# 03-POWER.net
KiCad netlist of a schematic drawn in Altium Designer
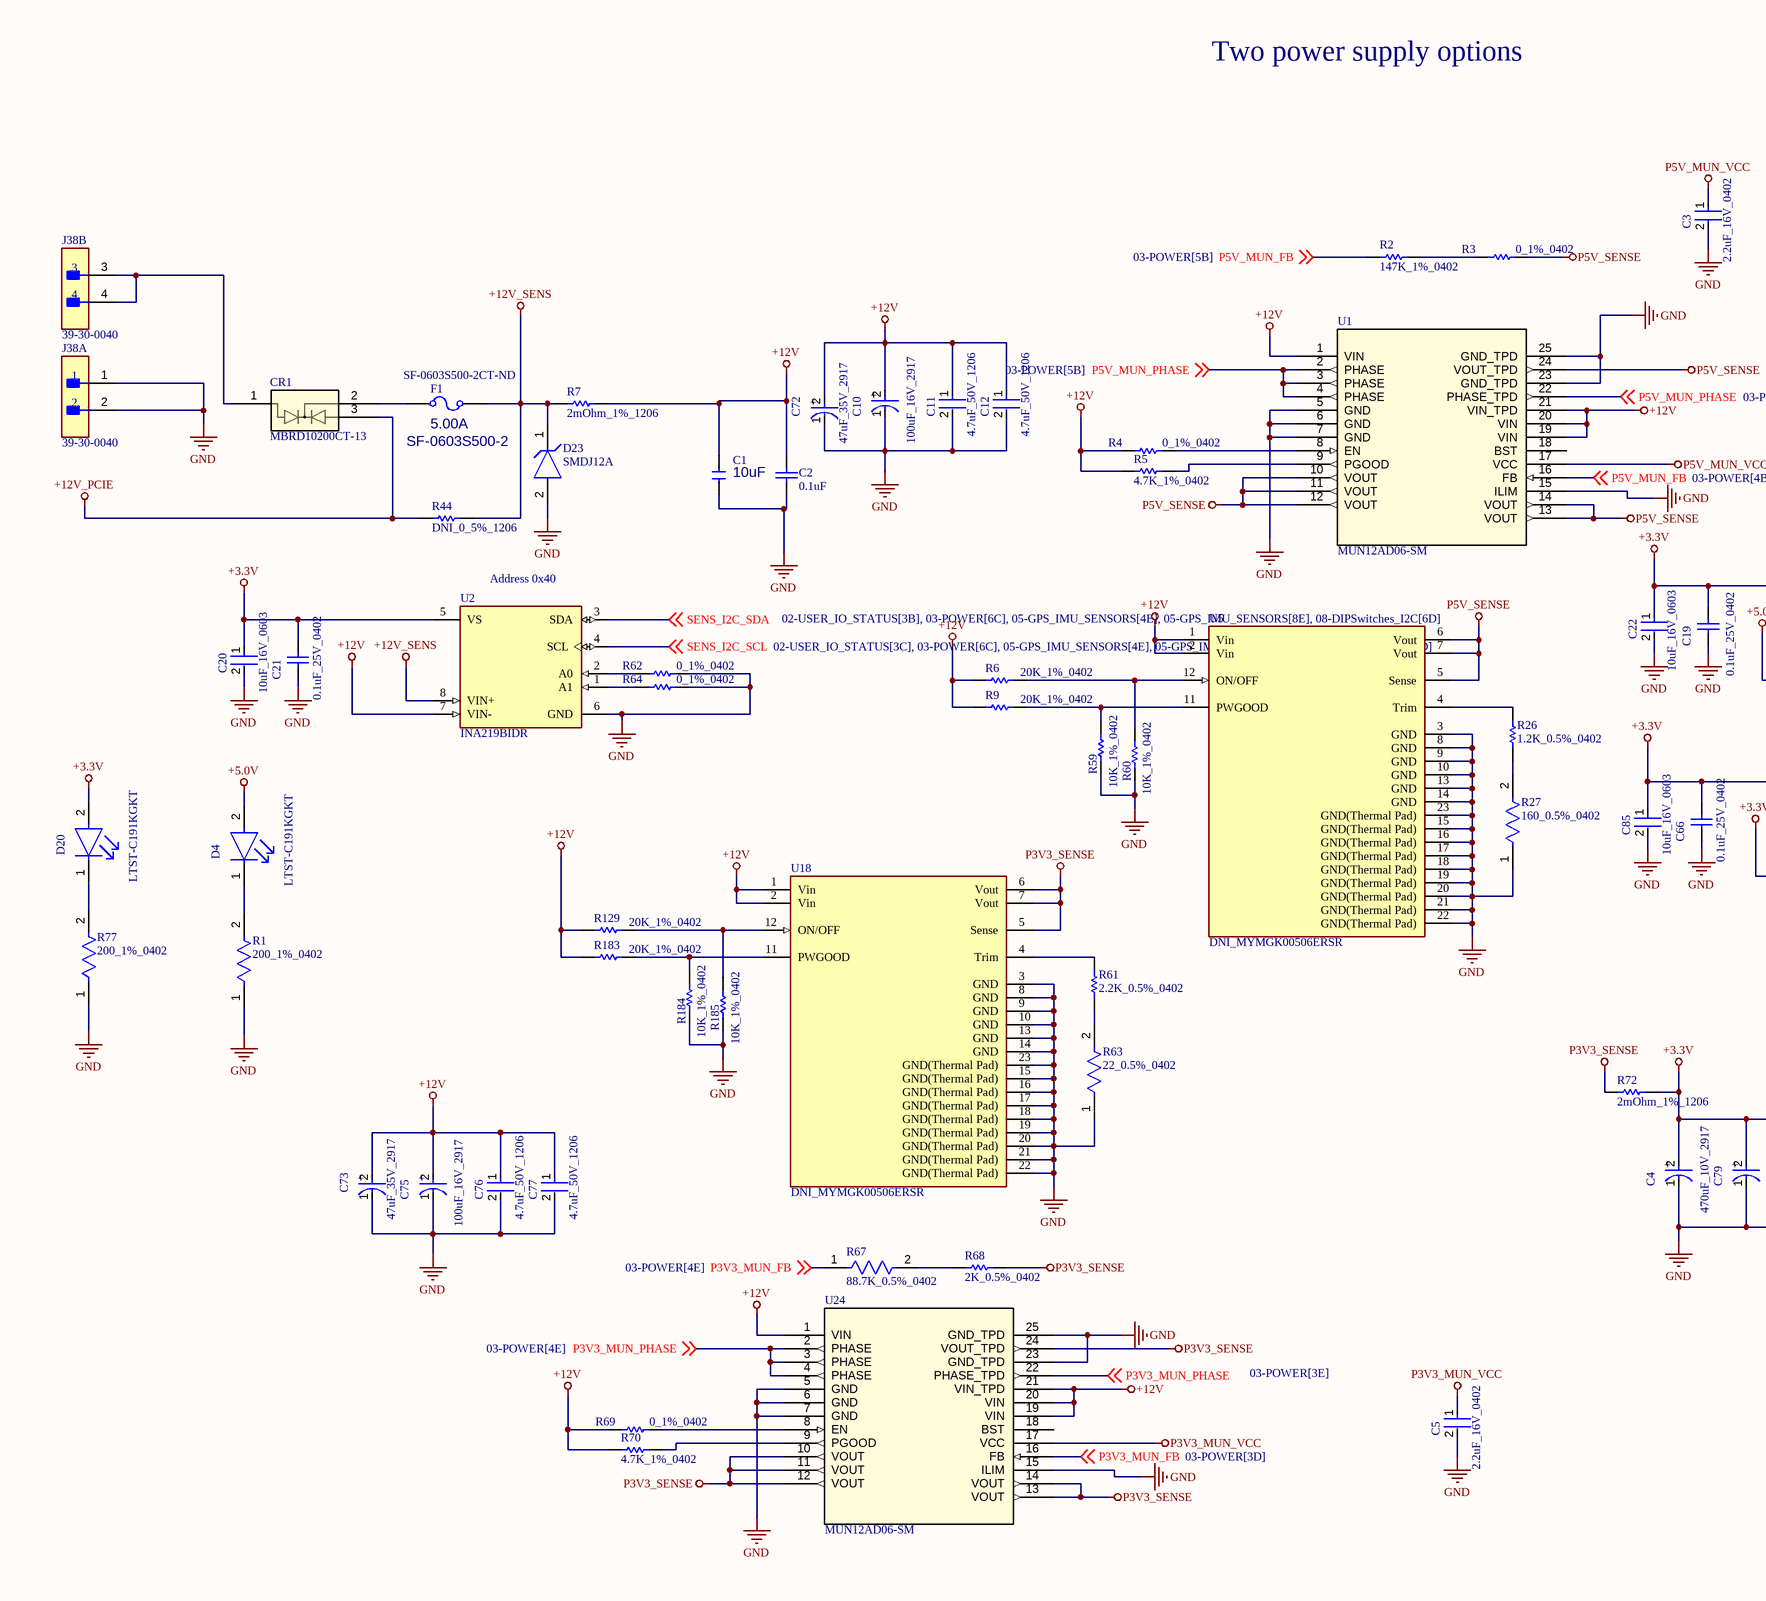
[diagram p0: 03-POWER.SchDoc, left]
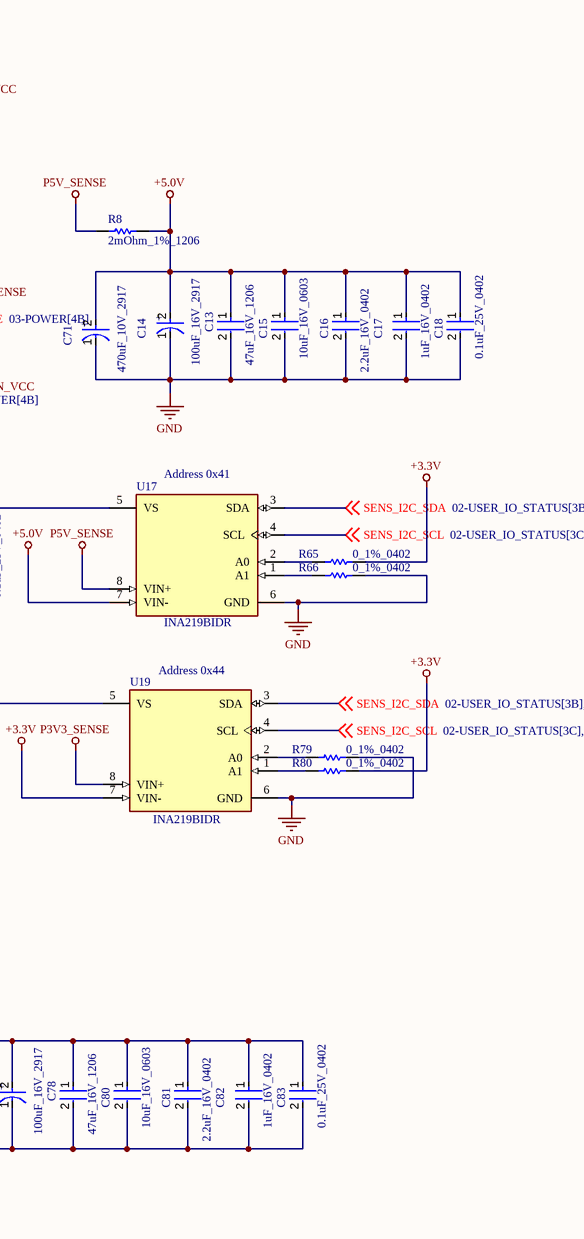
[diagram p1: 03-POWER.SchDoc, right]

(export (version "E")
  (design (tool "Eeschema 10.0.6"))
  (components
    (comp (ref "C1")
      (value "10uF")
      (footprint "CAPC2012X14N")
      (description "CAP, CER, 10.UF, 25V, 10%, X5R, 0805")
      (fields
        (field (name "MFG PART NUM") "TMK212BBJ106KG-T")
        (field (name "VALENTIUM PART NUM") "<VALENTIUM>")
      )
      (libsource (lib "Capacitors") (part "CAP_0805_10UF_25V"))
    )
    (comp (ref "C2")
      (value "0.1uF")
      (footprint "CAPC1608X87X45ML20T05")
      (description "C0603X104K5RACAUTO")
      (fields (field (name "MANUFACTURER") "Kemet"))
      (libsource (lib "Altium Content Vault") (part "CAP"))
    )
    (comp (ref "C3")
      (value "2.2uF_16V_0402")
      (footprint "FP-C1005-050-0_05-IPC_A")
      (description "Multilayer Ceramic Capacitors 2.2μF ±10% 16V X5R SMD 0402")
      (fields (field (name "TOLERANCE") "10%"))
      (libsource (lib "Altium Content Vault") (part "b4654b650e69147ec39a6b967a45e02"))
    )
    (comp (ref "C4")
      (value "470uF_10V_2917")
      (footprint "FP-TAJE-MFG")
      (description "470uF 10V  ±10% 500mΩ 2917  SMD Tantalum Capacitor")
      (fields (field (name "TOLERANCE") "10%") (field (name "VOLTAGE") "10V"))
      (libsource (lib "Altium Content Vault") (part "203bc49f2ac43e59fd269a8c329ed05"))
    )
    (comp (ref "C5")
      (value "2.2uF_16V_0402")
      (footprint "FP-C1005-050-0_05-IPC_A")
      (description "Multilayer Ceramic Capacitors 2.2μF ±10% 16V X5R SMD 0402")
      (fields (field (name "TOLERANCE") "10%"))
      (libsource (lib "Altium Content Vault") (part "b4654b650e69147ec39a6b967a45e02"))
    )
    (comp (ref "C10")
      (value "100uF_16V_2917")
      (footprint "FP-T495D107K016ATE125-MFG")
      (description "CAP TANT 100UF 10% 16V 2917")
      (fields (field (name "VOLTAGE") "16V") (field (name "TOLERANCE") "10%"))
      (libsource (lib "Altium Content Vault") (part "a00bbbee19879c290e62620ae7e47b1"))
    )
    (comp (ref "C11")
      (value "4.7uF_50V_1206")
      (footprint "FP-GRM31C-0_2-e0_3_0_8-IPC_C")
      (description "Chip Multilayer Ceramic Capacitors for General Purpose, 1206, 4.7uF, X7R, 15%, 10%, 50V")
      (fields (field (name "VOLTAGE") "50V") (field (name "TOLERANCE") "10%"))
      (libsource (lib "Altium Content Vault") (part "02cd4be3c70576c341d710602a673aa"))
    )
    (comp (ref "C12")
      (value "4.7uF_50V_1206")
      (footprint "FP-GRM31C-0_2-e0_3_0_8-IPC_C")
      (description "Chip Multilayer Ceramic Capacitors for General Purpose, 1206, 4.7uF, X7R, 15%, 10%, 50V")
      (fields (field (name "VOLTAGE") "50V") (field (name "TOLERANCE") "10%"))
      (libsource (lib "Altium Content Vault") (part "02cd4be3c70576c341d710602a673aa"))
    )
    (comp (ref "C13")
      (value "47uF_16V_1206")
      (footprint "FP-C3216-160-0_2-MFG")
      (description "Multilayer Ceramic Capacitors 47uF ±20% 16V X5R SMD 1206")
      (fields (field (name "TOLERANCE") "20%"))
      (libsource (lib "Altium Content Vault") (part "11868f565c42a9108669ba33697ecf6"))
    )
    (comp (ref "C14")
      (value "100uF_16V_2917")
      (footprint "FP-T495D107K016ATE125-MFG")
      (description "CAP TANT 100UF 10% 16V 2917")
      (fields (field (name "VOLTAGE") "16V") (field (name "TOLERANCE") "10%"))
      (libsource (lib "Altium Content Vault") (part "a00bbbee19879c290e62620ae7e47b1"))
    )
    (comp (ref "C15")
      (value "10uF_16V_0603")
      (footprint "FP-0603-L_1_6_0_2-W_0_8_0-MFG")
      (description "Multilayer Ceramic Capacitor 10uF 16V X5R 20% SMD 0603 T/R")
      (fields (field (name "TOLERANCE") "20%"))
      (libsource (lib "Altium Content Vault") (part "b4654b650e69147ec39a6b967a45e02"))
    )
    (comp (ref "C16")
      (value "2.2uF_16V_0402")
      (footprint "FP-C1005-050-0_05-IPC_A")
      (description "Multilayer Ceramic Capacitors 2.2μF ±10% 16V X5R SMD 0402")
      (fields (field (name "TOLERANCE") "10%"))
      (libsource (lib "Altium Content Vault") (part "b4654b650e69147ec39a6b967a45e02"))
    )
    (comp (ref "C17")
      (value "1uF_16V_0402")
      (footprint "FP-0402-L_1_0_0_05-W_0_5-IPC_A")
      (description "None")
      (fields (field (name "TOLERANCE") "10%"))
      (libsource (lib "Altium Content Vault") (part "b4654b650e69147ec39a6b967a45e02"))
    )
    (comp (ref "C18")
      (value "0.1uF_25V_0402")
      (footprint "FP-0402-L_1_0_1-W_0_5_0_1-IPC_C")
      (description "General Purpose Ceramic Capacitor, 0402, 100nF, 10%, X7R, 15%, 25V")
      (fields (field (name "VOLTAGE") "25V") (field (name "TOLERANCE") "10%"))
      (libsource (lib "Altium Content Vault") (part "b4654b650e69147ec39a6b967a45e02"))
    )
    (comp (ref "C19")
      (value "0.1uF_25V_0402")
      (footprint "CAPC1005X56X25NL10T15")
      (fields
        (field (name "PART NUMBER") "04023D104KAT2A")
        (field (name "MANUFACTURER") "AVX Interconnect / Elco")
      )
      (libsource (lib "Altium Content Vault") (part "CAP"))
    )
    (comp (ref "C20")
      (value "10uF_16V_0603")
      (footprint "FP-0603-L_1_6_0_2-W_0_8_0-MFG")
      (description "Multilayer Ceramic Capacitor 10uF 16V X5R 20% SMD 0603 T/R")
      (fields (field (name "TOLERANCE") "20%"))
      (libsource (lib "Altium Content Vault") (part "b4654b650e69147ec39a6b967a45e02"))
    )
    (comp (ref "C21")
      (value "0.1uF_25V_0402")
      (footprint "CAPC1005X56X25NL10T15")
      (fields
        (field (name "PART NUMBER") "04023D104KAT2A")
        (field (name "MANUFACTURER") "AVX Interconnect / Elco")
      )
      (libsource (lib "Altium Content Vault") (part "CAP"))
    )
    (comp (ref "C22")
      (value "10uF_16V_0603")
      (footprint "FP-0603-L_1_6_0_2-W_0_8_0-MFG")
      (description "Multilayer Ceramic Capacitor 10uF 16V X5R 20% SMD 0603 T/R")
      (fields (field (name "TOLERANCE") "20%"))
      (libsource (lib "Altium Content Vault") (part "b4654b650e69147ec39a6b967a45e02"))
    )
    (comp (ref "C66")
      (value "0.1uF_25V_0402")
      (footprint "CAPC1005X56X25NL10T15")
      (fields
        (field (name "PART NUMBER") "04023D104KAT2A")
        (field (name "MANUFACTURER") "AVX Interconnect / Elco")
      )
      (libsource (lib "Altium Content Vault") (part "CAP"))
    )
    (comp (ref "C71")
      (value "470uF_10V_2917")
      (footprint "FP-TAJE-MFG")
      (description "470uF 10V  ±10% 500mΩ 2917  SMD Tantalum Capacitor")
      (fields (field (name "TOLERANCE") "10%") (field (name "VOLTAGE") "10V"))
      (libsource (lib "Altium Content Vault") (part "203bc49f2ac43e59fd269a8c329ed05"))
    )
    (comp (ref "C72")
      (value "47uF_35V_2917")
      (footprint "FP-T521X476M035ATE030-MFG")
      (description "CAP TANT POLY 47UF 35V 2917")
      (fields (field (name "TOLERANCE") "20%"))
      (libsource (lib "Altium Content Vault") (part "a00bbbee19879c290e62620ae7e47b1"))
    )
    (comp (ref "C73")
      (value "47uF_35V_2917")
      (footprint "FP-T521X476M035ATE030-MFG")
      (description "CAP TANT POLY 47UF 35V 2917")
      (fields (field (name "TOLERANCE") "20%"))
      (libsource (lib "Altium Content Vault") (part "a00bbbee19879c290e62620ae7e47b1"))
    )
    (comp (ref "C75")
      (value "100uF_16V_2917")
      (footprint "FP-T495D107K016ATE125-MFG")
      (description "CAP TANT 100UF 10% 16V 2917")
      (fields (field (name "VOLTAGE") "16V") (field (name "TOLERANCE") "10%"))
      (libsource (lib "Altium Content Vault") (part "a00bbbee19879c290e62620ae7e47b1"))
    )
    (comp (ref "C76")
      (value "4.7uF_50V_1206")
      (footprint "FP-GRM31C-0_2-e0_3_0_8-IPC_C")
      (description "Chip Multilayer Ceramic Capacitors for General Purpose, 1206, 4.7uF, X7R, 15%, 10%, 50V")
      (fields (field (name "VOLTAGE") "50V") (field (name "TOLERANCE") "10%"))
      (libsource (lib "Altium Content Vault") (part "02cd4be3c70576c341d710602a673aa"))
    )
    (comp (ref "C77")
      (value "4.7uF_50V_1206")
      (footprint "FP-GRM31C-0_2-e0_3_0_8-IPC_C")
      (description "Chip Multilayer Ceramic Capacitors for General Purpose, 1206, 4.7uF, X7R, 15%, 10%, 50V")
      (fields (field (name "VOLTAGE") "50V") (field (name "TOLERANCE") "10%"))
      (libsource (lib "Altium Content Vault") (part "02cd4be3c70576c341d710602a673aa"))
    )
    (comp (ref "C78")
      (value "47uF_16V_1206")
      (footprint "FP-C3216-160-0_2-MFG")
      (description "Multilayer Ceramic Capacitors 47uF ±20% 16V X5R SMD 1206")
      (fields (field (name "TOLERANCE") "20%"))
      (libsource (lib "Altium Content Vault") (part "11868f565c42a9108669ba33697ecf6"))
    )
    (comp (ref "C79")
      (value "100uF_16V_2917")
      (footprint "FP-T495D107K016ATE125-MFG")
      (description "CAP TANT 100UF 10% 16V 2917")
      (fields (field (name "VOLTAGE") "16V") (field (name "TOLERANCE") "10%"))
      (libsource (lib "Altium Content Vault") (part "a00bbbee19879c290e62620ae7e47b1"))
    )
    (comp (ref "C80")
      (value "10uF_16V_0603")
      (footprint "FP-0603-L_1_6_0_2-W_0_8_0-MFG")
      (description "Multilayer Ceramic Capacitor 10uF 16V X5R 20% SMD 0603 T/R")
      (fields (field (name "TOLERANCE") "20%"))
      (libsource (lib "Altium Content Vault") (part "b4654b650e69147ec39a6b967a45e02"))
    )
    (comp (ref "C81")
      (value "2.2uF_16V_0402")
      (footprint "FP-C1005-050-0_05-IPC_A")
      (description "Multilayer Ceramic Capacitors 2.2μF ±10% 16V X5R SMD 0402")
      (fields (field (name "TOLERANCE") "10%"))
      (libsource (lib "Altium Content Vault") (part "b4654b650e69147ec39a6b967a45e02"))
    )
    (comp (ref "C82")
      (value "1uF_16V_0402")
      (footprint "FP-0402-L_1_0_0_05-W_0_5-IPC_A")
      (description "None")
      (fields (field (name "TOLERANCE") "10%"))
      (libsource (lib "Altium Content Vault") (part "b4654b650e69147ec39a6b967a45e02"))
    )
    (comp (ref "C83")
      (value "0.1uF_25V_0402")
      (footprint "FP-0402-L_1_0_1-W_0_5_0_1-IPC_C")
      (description "General Purpose Ceramic Capacitor, 0402, 100nF, 10%, X7R, 15%, 25V")
      (fields (field (name "VOLTAGE") "25V") (field (name "TOLERANCE") "10%"))
      (libsource (lib "Altium Content Vault") (part "b4654b650e69147ec39a6b967a45e02"))
    )
    (comp (ref "C85")
      (value "10uF_16V_0603")
      (footprint "FP-0603-L_1_6_0_2-W_0_8_0-MFG")
      (description "Multilayer Ceramic Capacitor 10uF 16V X5R 20% SMD 0603 T/R")
      (fields (field (name "TOLERANCE") "20%"))
      (libsource (lib "Altium Content Vault") (part "b4654b650e69147ec39a6b967a45e02"))
    )
    (comp (ref "CR1")
      (value "MBRD10200CT-13")
      (footprint "TO252(DPAK)_DIO")
      (description "No Description Available")
      (libsource (lib "MBRD10200CT-13") (part "MBRD10200CT-13"))
    )
    (comp (ref "D4")
      (value "LTST-C191KGKT")
      (footprint "FP-LTST-C191KGKT-MFG")
      (description "LED GREEN CLEAR SMD")
      (libsource (lib "Altium Content Vault") (part "8706943c75ba83719d021d2fdc84c58"))
    )
    (comp (ref "D20")
      (value "LTST-C191KGKT")
      (footprint "FP-LTST-C191KGKT-MFG")
      (description "LED GREEN CLEAR SMD")
      (libsource (lib "Altium Content Vault") (part "8706943c75ba83719d021d2fdc84c58"))
    )
    (comp (ref "D23")
      (value "SMDJ12A")
      (footprint "FP-DO-214AB_SMC_J-Bend-MFG")
      (description "TVS DIODE 12V 19.9V DO214AB")
      (libsource (lib "Altium Content Vault") (part "673ecd2ea4d7fb87b4005b0cb348b7d"))
    )
    (comp (ref "F1")
      (value "5.00A")
      (footprint "FUSM1608X60N")
      (description "FUSE SLOW 5.00A 32V M 0603")
      (fields
        (field (name "MFG PART NUM") "SF-0603S500-2")
        (field (name "VALENTIUM PART NUM") "<VALENTIUM>")
        (field (name "SUPPLIER PART NUMBER 1") "SF-0603S500-2CT-ND")
        (field (name "Comment") "FUSE_0603_5.00A")
      )
      (libsource (lib "Passives") (part "FUSE_0603_2.00A"))
    )
    (comp (ref "J38")
      (value "39-30-0040")
      (footprint "FP-39-30-0040-MFG")
      (description "CONN HEADER R/A 4POS 4.2MM")
      (fields
        (field (name "OCTOPART") "https://octopart.com/39-30-0040-molex-277428")
        (field (name "MANUFACTURER") "Molex")
      )
      (libsource (lib "Altium Content Vault") (part "ac72c5313ea981db199dbd0e8237b04"))
    )
    (comp (ref "R1")
      (value "200_1%_0402")
      (footprint "FP-ERJ2RK-IPC_A")
      (description "RES SMD 200 OHM 1% 1/10W 0402")
      (fields (field (name "TOLERANCE") "1%"))
      (libsource (lib "Altium Content Vault") (part "1029c3af85768c4190bb7ad29bc67b5"))
    )
    (comp (ref "R2")
      (value "147K_1%_0402")
      (footprint "RESC1005X40X25ML05T10")
      (fields (field (name "MANUFACTURER") "Yageo / Phycomp") (field (name "PART NUMBER") "RC0402FR-07147KL"))
      (libsource (lib "Altium Content Vault") (part "RES"))
    )
    (comp (ref "R3")
      (value "0_1%_0402")
      (footprint "RESC1005X40X25LL05T05")
      (description "Chip Resistor, 0 Ohm, 0.1 W, -55 to 155 degC, 0402 (1005 Metric), RoHS, Tape and Reel")
      (fields (field (name "MANUFACTURER") "Panasonic") (field (name "TOLERANCE") "5%"))
      (libsource (lib "Altium Content Vault") (part "RES-2"))
    )
    (comp (ref "R4")
      (value "0_1%_0402")
      (footprint "RESC1005X40X25LL05T05")
      (description "Chip Resistor, 0 Ohm, 0.1 W, -55 to 155 degC, 0402 (1005 Metric), RoHS, Tape and Reel")
      (fields (field (name "MANUFACTURER") "Panasonic") (field (name "TOLERANCE") "5%"))
      (libsource (lib "Altium Content Vault") (part "RES-2"))
    )
    (comp (ref "R5")
      (value "4.7K_1%_0402")
      (footprint "RESC1005X40X25NL10T10")
      (fields (field (name "MANUFACTURER") "Bourns") (field (name "PART NUMBER") "CR0402-FX-4701GLF"))
      (libsource (lib "Altium Content Vault") (part "RES"))
    )
    (comp (ref "R6")
      (value "20K_1%_0402")
      (footprint "RESC1005X40X25NL10T10")
      (fields (field (name "PART NUMBER") "MC00625W0402120K") (field (name "MANUFACTURER") "Multicomp"))
      (libsource (lib "Altium Content Vault") (part "RES"))
    )
    (comp (ref "R7")
      (value "2mOhm_1%_1206")
      (footprint "RESC3216X89X64NL25T25")
      (fields (field (name "MANUFACTURER") "Vishay Dale") (field (name "PART NUMBER") "WSL12062L000FEA18"))
      (libsource (lib "Altium Content Vault") (part "RES"))
    )
    (comp (ref "R8")
      (value "2mOhm_1%_1206")
      (footprint "RESC3216X89X64NL25T25")
      (fields (field (name "MANUFACTURER") "Vishay Dale") (field (name "PART NUMBER") "WSL12062L000FEA18"))
      (libsource (lib "Altium Content Vault") (part "RES"))
    )
    (comp (ref "R9")
      (value "20K_1%_0402")
      (footprint "RESC1005X40X25NL10T10")
      (fields (field (name "PART NUMBER") "MC00625W0402120K") (field (name "MANUFACTURER") "Multicomp"))
      (libsource (lib "Altium Content Vault") (part "RES"))
    )
    (comp (ref "R26")
      (value "1.2K_0.5%_0402")
      (footprint "RESC1005X40X25ML10T10")
      (fields (field (name "PART NUMBER") "ERA-2AED122X") (field (name "MANUFACTURER") "Panasonic"))
      (libsource (lib "Altium Content Vault") (part "RES"))
    )
    (comp (ref "R27")
      (value "160_0.5%_0402")
      (footprint "FP-RT0402-MFG")
      (description "RES SMD 160 OHM 0.5% 1/16W 0402")
      (fields
        (field (name "TOLERANCE") "0.005")
        (field (name "OCTOPART") "https://octopart.com/rt0402dre07160rl-yageo-1216058")
      )
      (libsource (lib "Altium Content Vault") (part "1029c3af85768c4190bb7ad29bc67b5"))
    )
    (comp (ref "R44")
      (value "DNI_0_5%_1206")
      (footprint "RESC3116X65X50ML20T20")
      (fields (field (name "PART NUMBER") "CRCW12060000Z0EAHP") (field (name "MANUFACTURER") "Vishay Dale"))
      (libsource (lib "Altium Content Vault") (part "RES"))
    )
    (comp (ref "R59")
      (value "10K_1%_0402")
      (footprint "RESC1005X40X25NL10T10")
      (fields (field (name "MANUFACTURER") "Bourns") (field (name "PART NUMBER") "CR0402-FX-1002GLF"))
      (libsource (lib "Altium Content Vault") (part "RES"))
    )
    (comp (ref "R60")
      (value "10K_1%_0402")
      (footprint "RESC1005X40X25NL10T10")
      (fields (field (name "MANUFACTURER") "Bourns") (field (name "PART NUMBER") "CR0402-FX-1002GLF"))
      (libsource (lib "Altium Content Vault") (part "RES"))
    )
    (comp (ref "R61")
      (value "2.2K_0.5%_0402")
      (footprint "RESC1005X40X25ML10T10")
      (fields (field (name "PART NUMBER") "ERA-2AED222X") (field (name "MANUFACTURER") "Panasonic"))
      (libsource (lib "Altium Content Vault") (part "RES"))
    )
    (comp (ref "R62")
      (value "0_1%_0402")
      (footprint "RESC1005X40X25LL05T05")
      (description "Chip Resistor, 0 Ohm, 0.1 W, -55 to 155 degC, 0402 (1005 Metric), RoHS, Tape and Reel")
      (fields (field (name "MANUFACTURER") "Panasonic") (field (name "TOLERANCE") "5%"))
      (libsource (lib "Altium Content Vault") (part "RES-2"))
    )
    (comp (ref "R63")
      (value "22_0.5%_0402")
      (footprint "FP-RG1005-IPC_A")
      (description "Automotive Metal Thin Film Chip Resistor, 0402, 22Ω, 0.5%, 100ppm/°C, 0.0625W, 75V")
      (fields (field (name "TOLERANCE") "0.5%"))
      (libsource (lib "Altium Content Vault") (part "1029c3af85768c4190bb7ad29bc67b5"))
    )
    (comp (ref "R64")
      (value "0_1%_0402")
      (footprint "RESC1005X40X25LL05T05")
      (description "Chip Resistor, 0 Ohm, 0.1 W, -55 to 155 degC, 0402 (1005 Metric), RoHS, Tape and Reel")
      (fields (field (name "MANUFACTURER") "Panasonic") (field (name "TOLERANCE") "5%"))
      (libsource (lib "Altium Content Vault") (part "RES-2"))
    )
    (comp (ref "R65")
      (value "0_1%_0402")
      (footprint "RESC1005X40X25LL05T05")
      (description "Chip Resistor, 0 Ohm, 0.1 W, -55 to 155 degC, 0402 (1005 Metric), RoHS, Tape and Reel")
      (fields (field (name "MANUFACTURER") "Panasonic") (field (name "TOLERANCE") "5%"))
      (libsource (lib "Altium Content Vault") (part "RES-2"))
    )
    (comp (ref "R66")
      (value "0_1%_0402")
      (footprint "RESC1005X40X25LL05T05")
      (description "Chip Resistor, 0 Ohm, 0.1 W, -55 to 155 degC, 0402 (1005 Metric), RoHS, Tape and Reel")
      (fields (field (name "MANUFACTURER") "Panasonic") (field (name "TOLERANCE") "5%"))
      (libsource (lib "Altium Content Vault") (part "RES-2"))
    )
    (comp (ref "R67")
      (value "88.7K_0.5%_0402")
      (footprint "FP-RT0402-MFG")
      (description "RES SMD 88.7K OHM 0.5% 1/16W")
      (fields
        (field (name "OCTOPART") "https://octopart.com/rt0402dre0788k7l-yageo-1439224")
        (field (name "MANUFACTURER") "Yageo")
      )
      (libsource (lib "Altium Content Vault") (part "1029c3af85768c4190bb7ad29bc67b5"))
    )
    (comp (ref "R68")
      (value "2K_0.5%_0402")
      (footprint "RESC1005X35X25LL10T10")
      (fields (field (name "PART NUMBER") "RT0402DRD072KL") (field (name "MANUFACTURER") "Yageo"))
      (libsource (lib "Altium Content Vault") (part "RES"))
    )
    (comp (ref "R69")
      (value "0_1%_0402")
      (footprint "RESC1005X40X25LL05T05")
      (description "Chip Resistor, 0 Ohm, 0.1 W, -55 to 155 degC, 0402 (1005 Metric), RoHS, Tape and Reel")
      (fields (field (name "MANUFACTURER") "Panasonic") (field (name "TOLERANCE") "5%"))
      (libsource (lib "Altium Content Vault") (part "RES-2"))
    )
    (comp (ref "R70")
      (value "4.7K_1%_0402")
      (footprint "RESC1005X40X25NL10T10")
      (fields (field (name "MANUFACTURER") "Bourns") (field (name "PART NUMBER") "CR0402-FX-4701GLF"))
      (libsource (lib "Altium Content Vault") (part "RES"))
    )
    (comp (ref "R72")
      (value "2mOhm_1%_1206")
      (footprint "RESC3216X89X64NL25T25")
      (fields (field (name "MANUFACTURER") "Vishay Dale") (field (name "PART NUMBER") "WSL12062L000FEA18"))
      (libsource (lib "Altium Content Vault") (part "RES"))
    )
    (comp (ref "R77")
      (value "200_1%_0402")
      (footprint "FP-ERJ2RK-IPC_A")
      (description "RES SMD 200 OHM 1% 1/10W 0402")
      (fields (field (name "TOLERANCE") "1%"))
      (libsource (lib "Altium Content Vault") (part "1029c3af85768c4190bb7ad29bc67b5"))
    )
    (comp (ref "R79")
      (value "0_1%_0402")
      (footprint "RESC1005X40X25LL05T05")
      (description "Chip Resistor, 0 Ohm, 0.1 W, -55 to 155 degC, 0402 (1005 Metric), RoHS, Tape and Reel")
      (fields (field (name "MANUFACTURER") "Panasonic") (field (name "TOLERANCE") "5%"))
      (libsource (lib "Altium Content Vault") (part "RES-2"))
    )
    (comp (ref "R80")
      (value "0_1%_0402")
      (footprint "RESC1005X40X25LL05T05")
      (description "Chip Resistor, 0 Ohm, 0.1 W, -55 to 155 degC, 0402 (1005 Metric), RoHS, Tape and Reel")
      (fields (field (name "MANUFACTURER") "Panasonic") (field (name "TOLERANCE") "5%"))
      (libsource (lib "Altium Content Vault") (part "RES-2"))
    )
    (comp (ref "R129")
      (value "20K_1%_0402")
      (footprint "RESC1005X40X25NL10T10")
      (fields (field (name "PART NUMBER") "MC00625W0402120K") (field (name "MANUFACTURER") "Multicomp"))
      (libsource (lib "Altium Content Vault") (part "RES"))
    )
    (comp (ref "R183")
      (value "20K_1%_0402")
      (footprint "RESC1005X40X25NL10T10")
      (fields (field (name "PART NUMBER") "MC00625W0402120K") (field (name "MANUFACTURER") "Multicomp"))
      (libsource (lib "Altium Content Vault") (part "RES"))
    )
    (comp (ref "R184")
      (value "10K_1%_0402")
      (footprint "RESC1005X40X25NL10T10")
      (fields (field (name "MANUFACTURER") "Bourns") (field (name "PART NUMBER") "CR0402-FX-1002GLF"))
      (libsource (lib "Altium Content Vault") (part "RES"))
    )
    (comp (ref "R185")
      (value "10K_1%_0402")
      (footprint "RESC1005X40X25NL10T10")
      (fields (field (name "MANUFACTURER") "Bourns") (field (name "PART NUMBER") "CR0402-FX-1002GLF"))
      (libsource (lib "Altium Content Vault") (part "RES"))
    )
    (comp (ref "U1")
      (value "MUN12AD06-SM")
      (footprint "MUN12AD06-SM_CYN")
      (description "No Description Available")
      (libsource (lib "MUN12AD06-SM") (part "MUN12AD06-SM"))
    )
    (comp (ref "U2")
      (value "INA219BIDR")
      (footprint "FP-D0008A-MFG")
      (description "IC MONITOR PWR/CURR BIDIR 8-SOIC")
      (libsource (lib "Altium Content Vault") (part "41cc1aee4cbc9fa2660a15773fa0e79"))
    )
    (comp (ref "U5")
      (value "DNI_MYMGK00506ERSR")
      (footprint "FP-MYMGK-12-MFG")
      (description "DC DC CONVERTER 0.7-5V")
      (libsource (lib "Altium Content Vault") (part "57b8017c1ce60d7b1362a625e7a4ba1"))
    )
    (comp (ref "U17")
      (value "INA219BIDR")
      (footprint "FP-D0008A-MFG")
      (description "IC MONITOR PWR/CURR BIDIR 8-SOIC")
      (libsource (lib "Altium Content Vault") (part "41cc1aee4cbc9fa2660a15773fa0e79"))
    )
    (comp (ref "U18")
      (value "DNI_MYMGK00506ERSR")
      (footprint "FP-MYMGK-12-MFG")
      (description "DC DC CONVERTER 0.7-5V")
      (libsource (lib "Altium Content Vault") (part "57b8017c1ce60d7b1362a625e7a4ba1"))
    )
    (comp (ref "U19")
      (value "INA219BIDR")
      (footprint "FP-D0008A-MFG")
      (description "IC MONITOR PWR/CURR BIDIR 8-SOIC")
      (libsource (lib "Altium Content Vault") (part "41cc1aee4cbc9fa2660a15773fa0e79"))
    )
    (comp (ref "U24")
      (value "MUN12AD06-SM")
      (footprint "MUN12AD06-SM_CYN")
      (description "No Description Available")
      (libsource (lib "MUN12AD06-SM") (part "MUN12AD06-SM"))
    )
  )
  (nets
    (net (code "1") (name "+3.3V") (class "Default")
      (node (ref "C19") (pin "2") (pinfunction "2_2") (pintype "passive"))
      (node (ref "C20") (pin "1") (pinfunction "1_1") (pintype "passive"))
      (node (ref "C21") (pin "2") (pinfunction "2_2") (pintype "passive"))
      (node (ref "C22") (pin "1") (pinfunction "1_1") (pintype "passive"))
      (node (ref "C4") (pin "2") (pinfunction "A_2") (pintype "passive"))
      (node (ref "C66") (pin "2") (pinfunction "2_2") (pintype "passive"))
      (node (ref "C78") (pin "1") (pinfunction "1_1") (pintype "passive"))
      (node (ref "C79") (pin "2") (pinfunction "A_2") (pintype "passive"))
      (node (ref "C80") (pin "1") (pinfunction "1_1") (pintype "passive"))
      (node (ref "C81") (pin "1") (pinfunction "1_1") (pintype "passive"))
      (node (ref "C82") (pin "1") (pinfunction "1_1") (pintype "passive"))
      (node (ref "C83") (pin "1") (pinfunction "1_1") (pintype "passive"))
      (node (ref "C85") (pin "1") (pinfunction "1_1") (pintype "passive"))
      (node (ref "D20") (pin "2") (pinfunction "A_2") (pintype "passive"))
      (node (ref "R65") (pin "2") (pinfunction "2_2") (pintype "passive"))
      (node (ref "R72") (pin "2") (pinfunction "2_2") (pintype "passive"))
      (node (ref "R80") (pin "2") (pinfunction "2_2") (pintype "passive"))
      (node (ref "U17") (pin "5") (pinfunction "VS_5") (pintype "power_in"))
      (node (ref "U19") (pin "5") (pinfunction "VS_5") (pintype "power_in"))
      (node (ref "U19") (pin "7") (pinfunction "VIN-_7") (pintype "input"))
      (node (ref "U2") (pin "5") (pinfunction "VS_5") (pintype "power_in"))
    )
    (net (code "2") (name "+5.0V") (class "Default")
      (node (ref "C13") (pin "1") (pinfunction "1_1") (pintype "passive"))
      (node (ref "C14") (pin "2") (pinfunction "A_2") (pintype "passive"))
      (node (ref "C15") (pin "1") (pinfunction "1_1") (pintype "passive"))
      (node (ref "C16") (pin "1") (pinfunction "1_1") (pintype "passive"))
      (node (ref "C17") (pin "1") (pinfunction "1_1") (pintype "passive"))
      (node (ref "C18") (pin "1") (pinfunction "1_1") (pintype "passive"))
      (node (ref "C71") (pin "2") (pinfunction "A_2") (pintype "passive"))
      (node (ref "D4") (pin "2") (pinfunction "A_2") (pintype "passive"))
      (node (ref "R8") (pin "2") (pinfunction "2_2") (pintype "passive"))
      (node (ref "U17") (pin "7") (pinfunction "VIN-_7") (pintype "input"))
    )
    (net (code "3") (name "+12V") (class "Default")
      (node (ref "C1") (pin "1") (pinfunction "1_1") (pintype "passive"))
      (node (ref "C10") (pin "2") (pinfunction "A_2") (pintype "passive"))
      (node (ref "C11") (pin "1") (pinfunction "1_1") (pintype "passive"))
      (node (ref "C12") (pin "1") (pinfunction "1_1") (pintype "passive"))
      (node (ref "C2") (pin "2") (pinfunction "2_2") (pintype "passive"))
      (node (ref "C72") (pin "2") (pinfunction "A_2") (pintype "passive"))
      (node (ref "C73") (pin "2") (pinfunction "A_2") (pintype "passive"))
      (node (ref "C75") (pin "2") (pinfunction "A_2") (pintype "passive"))
      (node (ref "C76") (pin "1") (pinfunction "1_1") (pintype "passive"))
      (node (ref "C77") (pin "1") (pinfunction "1_1") (pintype "passive"))
      (node (ref "R129") (pin "1") (pinfunction "1_1") (pintype "passive"))
      (node (ref "R183") (pin "1") (pinfunction "1_1") (pintype "passive"))
      (node (ref "R4") (pin "1") (pinfunction "1_1") (pintype "passive"))
      (node (ref "R5") (pin "2") (pinfunction "2_2") (pintype "passive"))
      (node (ref "R6") (pin "1") (pinfunction "1_1") (pintype "passive"))
      (node (ref "R69") (pin "1") (pinfunction "1_1") (pintype "passive"))
      (node (ref "R7") (pin "2") (pinfunction "2_2") (pintype "passive"))
      (node (ref "R70") (pin "2") (pinfunction "2_2") (pintype "passive"))
      (node (ref "R9") (pin "1") (pinfunction "1_1") (pintype "passive"))
      (node (ref "U1") (pin "1") (pinfunction "VIN_1") (pintype "power_in"))
      (node (ref "U1") (pin "19") (pinfunction "VIN_19") (pintype "power_in"))
      (node (ref "U1") (pin "20") (pinfunction "VIN_20") (pintype "power_in"))
      (node (ref "U1") (pin "21") (pinfunction "VIN_TPD_21") (pintype "power_in"))
      (node (ref "U18") (pin "1") (pinfunction "Vin_1") (pintype "power_in"))
      (node (ref "U18") (pin "2") (pinfunction "Vin_2") (pintype "power_in"))
      (node (ref "U2") (pin "7") (pinfunction "VIN-_7") (pintype "input"))
      (node (ref "U24") (pin "1") (pinfunction "VIN_1") (pintype "power_in"))
      (node (ref "U24") (pin "19") (pinfunction "VIN_19") (pintype "power_in"))
      (node (ref "U24") (pin "20") (pinfunction "VIN_20") (pintype "power_in"))
      (node (ref "U24") (pin "21") (pinfunction "VIN_TPD_21") (pintype "power_in"))
      (node (ref "U5") (pin "1") (pinfunction "Vin_1") (pintype "power_in"))
      (node (ref "U5") (pin "2") (pinfunction "Vin_2") (pintype "power_in"))
    )
    (net (code "4") (name "+12V_PCIE") (class "Default")
      (node (ref "CR1") (pin "3") (pinfunction "3_3") (pintype "passive"))
      (node (ref "R44") (pin "1") (pinfunction "1_1") (pintype "passive"))
    )
    (net (code "5") (name "+12V_SENS") (class "Default")
      (node (ref "D23") (pin "1") (pinfunction "C_1") (pintype "passive"))
      (node (ref "F1") (pin "2") (pinfunction "2_2") (pintype "passive"))
      (node (ref "R44") (pin "2") (pinfunction "2_2") (pintype "passive"))
      (node (ref "R7") (pin "1") (pinfunction "1_1") (pintype "passive"))
      (node (ref "U2") (pin "8") (pinfunction "VIN+_8") (pintype "input"))
    )
    (net (code "6") (name "GND") (class "Default")
      (node (ref "C1") (pin "2") (pinfunction "2_2") (pintype "passive"))
      (node (ref "C10") (pin "1") (pinfunction "C_1") (pintype "passive"))
      (node (ref "C11") (pin "2") (pinfunction "2_2") (pintype "passive"))
      (node (ref "C12") (pin "2") (pinfunction "2_2") (pintype "passive"))
      (node (ref "C13") (pin "2") (pinfunction "2_2") (pintype "passive"))
      (node (ref "C14") (pin "1") (pinfunction "C_1") (pintype "passive"))
      (node (ref "C15") (pin "2") (pinfunction "2_2") (pintype "passive"))
      (node (ref "C16") (pin "2") (pinfunction "2_2") (pintype "passive"))
      (node (ref "C17") (pin "2") (pinfunction "2_2") (pintype "passive"))
      (node (ref "C18") (pin "2") (pinfunction "2_2") (pintype "passive"))
      (node (ref "C19") (pin "1") (pinfunction "1_1") (pintype "passive"))
      (node (ref "C2") (pin "1") (pinfunction "1_1") (pintype "passive"))
      (node (ref "C20") (pin "2") (pinfunction "2_2") (pintype "passive"))
      (node (ref "C21") (pin "1") (pinfunction "1_1") (pintype "passive"))
      (node (ref "C22") (pin "2") (pinfunction "2_2") (pintype "passive"))
      (node (ref "C3") (pin "2") (pinfunction "2_2") (pintype "passive"))
      (node (ref "C4") (pin "1") (pinfunction "C_1") (pintype "passive"))
      (node (ref "C5") (pin "2") (pinfunction "2_2") (pintype "passive"))
      (node (ref "C66") (pin "1") (pinfunction "1_1") (pintype "passive"))
      (node (ref "C71") (pin "1") (pinfunction "C_1") (pintype "passive"))
      (node (ref "C72") (pin "1") (pinfunction "C_1") (pintype "passive"))
      (node (ref "C73") (pin "1") (pinfunction "C_1") (pintype "passive"))
      (node (ref "C75") (pin "1") (pinfunction "C_1") (pintype "passive"))
      (node (ref "C76") (pin "2") (pinfunction "2_2") (pintype "passive"))
      (node (ref "C77") (pin "2") (pinfunction "2_2") (pintype "passive"))
      (node (ref "C78") (pin "2") (pinfunction "2_2") (pintype "passive"))
      (node (ref "C79") (pin "1") (pinfunction "C_1") (pintype "passive"))
      (node (ref "C80") (pin "2") (pinfunction "2_2") (pintype "passive"))
      (node (ref "C81") (pin "2") (pinfunction "2_2") (pintype "passive"))
      (node (ref "C82") (pin "2") (pinfunction "2_2") (pintype "passive"))
      (node (ref "C83") (pin "2") (pinfunction "2_2") (pintype "passive"))
      (node (ref "C85") (pin "2") (pinfunction "2_2") (pintype "passive"))
      (node (ref "D23") (pin "2") (pinfunction "A_2") (pintype "passive"))
      (node (ref "J38") (pin "1") (pinfunction "1_1") (pintype "passive"))
      (node (ref "J38") (pin "2") (pinfunction "2_2") (pintype "passive"))
      (node (ref "R1") (pin "1") (pinfunction "1_1") (pintype "passive"))
      (node (ref "R184") (pin "1") (pinfunction "1_1") (pintype "passive"))
      (node (ref "R185") (pin "1") (pinfunction "1_1") (pintype "passive"))
      (node (ref "R27") (pin "1") (pinfunction "1_1") (pintype "passive"))
      (node (ref "R59") (pin "1") (pinfunction "1_1") (pintype "passive"))
      (node (ref "R60") (pin "1") (pinfunction "1_1") (pintype "passive"))
      (node (ref "R62") (pin "2") (pinfunction "2_2") (pintype "passive"))
      (node (ref "R63") (pin "1") (pinfunction "1_1") (pintype "passive"))
      (node (ref "R64") (pin "2") (pinfunction "2_2") (pintype "passive"))
      (node (ref "R66") (pin "2") (pinfunction "2_2") (pintype "passive"))
      (node (ref "R77") (pin "1") (pinfunction "1_1") (pintype "passive"))
      (node (ref "R79") (pin "2") (pinfunction "2_2") (pintype "passive"))
      (node (ref "U1") (pin "15") (pinfunction "ILIM_15") (pintype "passive"))
      (node (ref "U1") (pin "23") (pinfunction "GND_TPD_23") (pintype "power_in"))
      (node (ref "U1") (pin "25") (pinfunction "GND_TPD_25") (pintype "power_in"))
      (node (ref "U1") (pin "5") (pinfunction "GND_5") (pintype "power_in"))
      (node (ref "U1") (pin "6") (pinfunction "GND_6") (pintype "power_in"))
      (node (ref "U1") (pin "7") (pinfunction "GND_7") (pintype "power_in"))
      (node (ref "U17") (pin "6") (pinfunction "GND_6") (pintype "power_in"))
      (node (ref "U18") (pin "10") (pinfunction "GND_10") (pintype "power_in"))
      (node (ref "U18") (pin "13") (pinfunction "GND_13") (pintype "power_in"))
      (node (ref "U18") (pin "14") (pinfunction "GND_14") (pintype "power_in"))
      (node (ref "U18") (pin "15") (pinfunction "GND(Thermal_Pad)_15") (pintype "power_in"))
      (node (ref "U18") (pin "16") (pinfunction "GND(Thermal_Pad)_16") (pintype "power_in"))
      (node (ref "U18") (pin "17") (pinfunction "GND(Thermal_Pad)_17") (pintype "power_in"))
      (node (ref "U18") (pin "18") (pinfunction "GND(Thermal_Pad)_18") (pintype "power_in"))
      (node (ref "U18") (pin "19") (pinfunction "GND(Thermal_Pad)_19") (pintype "power_in"))
      (node (ref "U18") (pin "20") (pinfunction "GND(Thermal_Pad)_20") (pintype "power_in"))
      (node (ref "U18") (pin "21") (pinfunction "GND(Thermal_Pad)_21") (pintype "power_in"))
      (node (ref "U18") (pin "22") (pinfunction "GND(Thermal_Pad)_22") (pintype "power_in"))
      (node (ref "U18") (pin "23") (pinfunction "GND(Thermal_Pad)_23") (pintype "power_in"))
      (node (ref "U18") (pin "3") (pinfunction "GND_3") (pintype "power_in"))
      (node (ref "U18") (pin "8") (pinfunction "GND_8") (pintype "power_in"))
      (node (ref "U18") (pin "9") (pinfunction "GND_9") (pintype "power_in"))
      (node (ref "U19") (pin "6") (pinfunction "GND_6") (pintype "power_in"))
      (node (ref "U2") (pin "6") (pinfunction "GND_6") (pintype "power_in"))
      (node (ref "U24") (pin "15") (pinfunction "ILIM_15") (pintype "passive"))
      (node (ref "U24") (pin "23") (pinfunction "GND_TPD_23") (pintype "power_in"))
      (node (ref "U24") (pin "25") (pinfunction "GND_TPD_25") (pintype "power_in"))
      (node (ref "U24") (pin "5") (pinfunction "GND_5") (pintype "power_in"))
      (node (ref "U24") (pin "6") (pinfunction "GND_6") (pintype "power_in"))
      (node (ref "U24") (pin "7") (pinfunction "GND_7") (pintype "power_in"))
      (node (ref "U5") (pin "10") (pinfunction "GND_10") (pintype "power_in"))
      (node (ref "U5") (pin "13") (pinfunction "GND_13") (pintype "power_in"))
      (node (ref "U5") (pin "14") (pinfunction "GND_14") (pintype "power_in"))
      (node (ref "U5") (pin "15") (pinfunction "GND(Thermal_Pad)_15") (pintype "power_in"))
      (node (ref "U5") (pin "16") (pinfunction "GND(Thermal_Pad)_16") (pintype "power_in"))
      (node (ref "U5") (pin "17") (pinfunction "GND(Thermal_Pad)_17") (pintype "power_in"))
      (node (ref "U5") (pin "18") (pinfunction "GND(Thermal_Pad)_18") (pintype "power_in"))
      (node (ref "U5") (pin "19") (pinfunction "GND(Thermal_Pad)_19") (pintype "power_in"))
      (node (ref "U5") (pin "20") (pinfunction "GND(Thermal_Pad)_20") (pintype "power_in"))
      (node (ref "U5") (pin "21") (pinfunction "GND(Thermal_Pad)_21") (pintype "power_in"))
      (node (ref "U5") (pin "22") (pinfunction "GND(Thermal_Pad)_22") (pintype "power_in"))
      (node (ref "U5") (pin "23") (pinfunction "GND(Thermal_Pad)_23") (pintype "power_in"))
      (node (ref "U5") (pin "3") (pinfunction "GND_3") (pintype "power_in"))
      (node (ref "U5") (pin "8") (pinfunction "GND_8") (pintype "power_in"))
      (node (ref "U5") (pin "9") (pinfunction "GND_9") (pintype "power_in"))
    )
    (net (code "7") (name "Net-(CR1-Pad1)") (class "Default")
      (node (ref "CR1") (pin "1") (pinfunction "1_1") (pintype "passive"))
      (node (ref "J38") (pin "3") (pinfunction "3_3") (pintype "passive"))
      (node (ref "J38") (pin "4") (pinfunction "4_4") (pintype "passive"))
    )
    (net (code "8") (name "Net-(CR1-Pad2)") (class "Default")
      (node (ref "CR1") (pin "2") (pinfunction "2_2") (pintype "passive"))
      (node (ref "F1") (pin "1") (pinfunction "1_1") (pintype "passive"))
    )
    (net (code "9") (name "Net-(D4-C)") (class "Default")
      (node (ref "D4") (pin "1") (pinfunction "C_1") (pintype "passive"))
      (node (ref "R1") (pin "2") (pinfunction "2_2") (pintype "passive"))
    )
    (net (code "10") (name "Net-(D20-C)") (class "Default")
      (node (ref "D20") (pin "1") (pinfunction "C_1") (pintype "passive"))
      (node (ref "R77") (pin "2") (pinfunction "2_2") (pintype "passive"))
    )
    (net (code "11") (name "Net-(R2-Pad2)") (class "Default")
      (node (ref "R2") (pin "2") (pinfunction "2_2") (pintype "passive"))
      (node (ref "R3") (pin "1") (pinfunction "1_1") (pintype "passive"))
    )
    (net (code "12") (name "Net-(R26-Pad1)") (class "Default")
      (node (ref "R26") (pin "1") (pinfunction "1_1") (pintype "passive"))
      (node (ref "R27") (pin "2") (pinfunction "2_2") (pintype "passive"))
    )
    (net (code "13") (name "Net-(R61-Pad1)") (class "Default")
      (node (ref "R61") (pin "1") (pinfunction "1_1") (pintype "passive"))
      (node (ref "R63") (pin "2") (pinfunction "2_2") (pintype "passive"))
    )
    (net (code "14") (name "Net-(R67-Pad2)") (class "Default")
      (node (ref "R67") (pin "2") (pinfunction "2_2") (pintype "passive"))
      (node (ref "R68") (pin "1") (pinfunction "1_1") (pintype "passive"))
    )
    (net (code "15") (name "Net-(U1-EN)") (class "Default")
      (node (ref "R4") (pin "2") (pinfunction "2_2") (pintype "passive"))
      (node (ref "U1") (pin "8") (pinfunction "EN_8") (pintype "input"))
    )
    (net (code "16") (name "Net-(U1-PGOOD)") (class "Default")
      (node (ref "R5") (pin "1") (pinfunction "1_1") (pintype "passive"))
      (node (ref "U1") (pin "9") (pinfunction "PGOOD_9") (pintype "output"))
    )
    (net (code "17") (name "Net-(U2-A0)") (class "Default")
      (node (ref "R62") (pin "1") (pinfunction "1_1") (pintype "passive"))
      (node (ref "U2") (pin "2") (pinfunction "A0_2") (pintype "input"))
    )
    (net (code "18") (name "Net-(U2-A1)") (class "Default")
      (node (ref "R64") (pin "1") (pinfunction "1_1") (pintype "passive"))
      (node (ref "U2") (pin "1") (pinfunction "A1_1") (pintype "input"))
    )
    (net (code "19") (name "Net-(U5-ON{slash}OFF)") (class "Default")
      (node (ref "R6") (pin "2") (pinfunction "2_2") (pintype "passive"))
      (node (ref "R60") (pin "2") (pinfunction "2_2") (pintype "passive"))
      (node (ref "U5") (pin "12") (pinfunction "ON/OFF_12") (pintype "input"))
    )
    (net (code "20") (name "Net-(U5-PWGOOD)") (class "Default")
      (node (ref "R59") (pin "2") (pinfunction "2_2") (pintype "passive"))
      (node (ref "R9") (pin "2") (pinfunction "2_2") (pintype "passive"))
      (node (ref "U5") (pin "11") (pinfunction "PWGOOD_11") (pintype "open_collector"))
    )
    (net (code "21") (name "Net-(U5-Trim)") (class "Default")
      (node (ref "R26") (pin "2") (pinfunction "2_2") (pintype "passive"))
      (node (ref "U5") (pin "4") (pinfunction "Trim_4") (pintype "passive"))
    )
    (net (code "22") (name "Net-(U17-A0)") (class "Default")
      (node (ref "R65") (pin "1") (pinfunction "1_1") (pintype "passive"))
      (node (ref "U17") (pin "2") (pinfunction "A0_2") (pintype "input"))
    )
    (net (code "23") (name "Net-(U17-A1)") (class "Default")
      (node (ref "R66") (pin "1") (pinfunction "1_1") (pintype "passive"))
      (node (ref "U17") (pin "1") (pinfunction "A1_1") (pintype "input"))
    )
    (net (code "24") (name "Net-(U18-ON{slash}OFF)") (class "Default")
      (node (ref "R129") (pin "2") (pinfunction "2_2") (pintype "passive"))
      (node (ref "R185") (pin "2") (pinfunction "2_2") (pintype "passive"))
      (node (ref "U18") (pin "12") (pinfunction "ON/OFF_12") (pintype "input"))
    )
    (net (code "25") (name "Net-(U18-PWGOOD)") (class "Default")
      (node (ref "R183") (pin "2") (pinfunction "2_2") (pintype "passive"))
      (node (ref "R184") (pin "2") (pinfunction "2_2") (pintype "passive"))
      (node (ref "U18") (pin "11") (pinfunction "PWGOOD_11") (pintype "open_collector"))
    )
    (net (code "26") (name "Net-(U18-Trim)") (class "Default")
      (node (ref "R61") (pin "2") (pinfunction "2_2") (pintype "passive"))
      (node (ref "U18") (pin "4") (pinfunction "Trim_4") (pintype "passive"))
    )
    (net (code "27") (name "Net-(U19-A0)") (class "Default")
      (node (ref "R79") (pin "1") (pinfunction "1_1") (pintype "passive"))
      (node (ref "U19") (pin "2") (pinfunction "A0_2") (pintype "input"))
    )
    (net (code "28") (name "Net-(U19-A1)") (class "Default")
      (node (ref "R80") (pin "1") (pinfunction "1_1") (pintype "passive"))
      (node (ref "U19") (pin "1") (pinfunction "A1_1") (pintype "input"))
    )
    (net (code "29") (name "Net-(U24-EN)") (class "Default")
      (node (ref "R69") (pin "2") (pinfunction "2_2") (pintype "passive"))
      (node (ref "U24") (pin "8") (pinfunction "EN_8") (pintype "input"))
    )
    (net (code "30") (name "Net-(U24-PGOOD)") (class "Default")
      (node (ref "R70") (pin "1") (pinfunction "1_1") (pintype "passive"))
      (node (ref "U24") (pin "9") (pinfunction "PGOOD_9") (pintype "output"))
    )
    (net (code "31") (name "P3V3_MUN_FB") (class "Default")
      (node (ref "R67") (pin "1") (pinfunction "1_1") (pintype "passive"))
      (node (ref "U24") (pin "16") (pinfunction "FB_16") (pintype "input"))
    )
    (net (code "32") (name "P3V3_MUN_PHASE") (class "Default")
      (node (ref "U24") (pin "2") (pinfunction "PHASE_2") (pintype "output"))
      (node (ref "U24") (pin "22") (pinfunction "PHASE_TPD_22") (pintype "output"))
      (node (ref "U24") (pin "3") (pinfunction "PHASE_3") (pintype "output"))
      (node (ref "U24") (pin "4") (pinfunction "PHASE_4") (pintype "output"))
    )
    (net (code "33") (name "P3V3_MUN_VCC") (class "Default")
      (node (ref "C5") (pin "1") (pinfunction "1_1") (pintype "passive"))
      (node (ref "U24") (pin "17") (pinfunction "VCC_17") (pintype "power_in"))
    )
    (net (code "34") (name "P3V3_SENSE") (class "Default")
      (node (ref "R68") (pin "2") (pinfunction "2_2") (pintype "passive"))
      (node (ref "R72") (pin "1") (pinfunction "1_1") (pintype "passive"))
      (node (ref "U18") (pin "5") (pinfunction "Sense_5") (pintype "passive"))
      (node (ref "U18") (pin "6") (pinfunction "Vout_6") (pintype "power_in"))
      (node (ref "U18") (pin "7") (pinfunction "Vout_7") (pintype "power_in"))
      (node (ref "U19") (pin "8") (pinfunction "VIN+_8") (pintype "input"))
      (node (ref "U24") (pin "10") (pinfunction "VOUT_10") (pintype "output"))
      (node (ref "U24") (pin "11") (pinfunction "VOUT_11") (pintype "output"))
      (node (ref "U24") (pin "12") (pinfunction "VOUT_12") (pintype "output"))
      (node (ref "U24") (pin "13") (pinfunction "VOUT_13") (pintype "output"))
      (node (ref "U24") (pin "14") (pinfunction "VOUT_14") (pintype "output"))
      (node (ref "U24") (pin "24") (pinfunction "VOUT_TPD_24") (pintype "output"))
    )
    (net (code "35") (name "P5V_MUN_FB") (class "Default")
      (node (ref "R2") (pin "1") (pinfunction "1_1") (pintype "passive"))
      (node (ref "U1") (pin "16") (pinfunction "FB_16") (pintype "input"))
    )
    (net (code "36") (name "P5V_MUN_PHASE") (class "Default")
      (node (ref "U1") (pin "2") (pinfunction "PHASE_2") (pintype "output"))
      (node (ref "U1") (pin "22") (pinfunction "PHASE_TPD_22") (pintype "output"))
      (node (ref "U1") (pin "3") (pinfunction "PHASE_3") (pintype "output"))
      (node (ref "U1") (pin "4") (pinfunction "PHASE_4") (pintype "output"))
    )
    (net (code "37") (name "P5V_MUN_VCC") (class "Default")
      (node (ref "C3") (pin "1") (pinfunction "1_1") (pintype "passive"))
      (node (ref "U1") (pin "17") (pinfunction "VCC_17") (pintype "power_in"))
    )
    (net (code "38") (name "P5V_SENSE") (class "Default")
      (node (ref "R3") (pin "2") (pinfunction "2_2") (pintype "passive"))
      (node (ref "R8") (pin "1") (pinfunction "1_1") (pintype "passive"))
      (node (ref "U1") (pin "10") (pinfunction "VOUT_10") (pintype "output"))
      (node (ref "U1") (pin "11") (pinfunction "VOUT_11") (pintype "output"))
      (node (ref "U1") (pin "12") (pinfunction "VOUT_12") (pintype "output"))
      (node (ref "U1") (pin "13") (pinfunction "VOUT_13") (pintype "output"))
      (node (ref "U1") (pin "14") (pinfunction "VOUT_14") (pintype "output"))
      (node (ref "U1") (pin "24") (pinfunction "VOUT_TPD_24") (pintype "output"))
      (node (ref "U17") (pin "8") (pinfunction "VIN+_8") (pintype "input"))
      (node (ref "U5") (pin "5") (pinfunction "Sense_5") (pintype "passive"))
      (node (ref "U5") (pin "6") (pinfunction "Vout_6") (pintype "power_in"))
      (node (ref "U5") (pin "7") (pinfunction "Vout_7") (pintype "power_in"))
    )
    (net (code "39") (name "SENS_I2C_SCL") (class "Default")
      (node (ref "U17") (pin "4") (pinfunction "SCL_4") (pintype "bidirectional"))
      (node (ref "U19") (pin "4") (pinfunction "SCL_4") (pintype "bidirectional"))
      (node (ref "U2") (pin "4") (pinfunction "SCL_4") (pintype "bidirectional"))
    )
    (net (code "40") (name "SENS_I2C_SDA") (class "Default")
      (node (ref "U17") (pin "3") (pinfunction "SDA_3") (pintype "bidirectional"))
      (node (ref "U19") (pin "3") (pinfunction "SDA_3") (pintype "bidirectional"))
      (node (ref "U2") (pin "3") (pinfunction "SDA_3") (pintype "bidirectional"))
    )
    (net (code "41") (name "unconnected-(U1-BST-Pad18)") (class "Default")
      (node (ref "U1") (pin "18") (pinfunction "BST_18") (pintype "power_in"))
    )
    (net (code "42") (name "unconnected-(U24-BST-Pad18)") (class "Default")
      (node (ref "U24") (pin "18") (pinfunction "BST_18") (pintype "power_in"))
    )
  )
)
